# AUX_POWER_-5V.net
KiCad netlist of a schematic drawn in Altium Designer
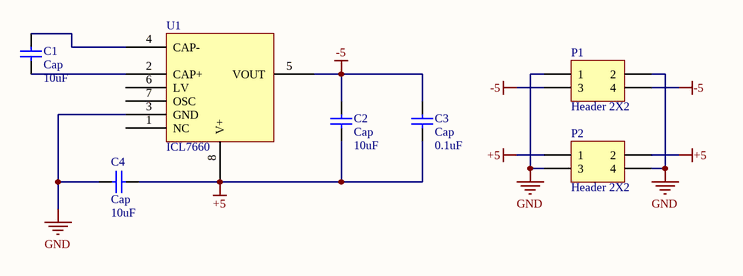
[diagram p0: AUX_POWER_-5V.SchDoc]

(export (version "E")
  (design (tool "Eeschema 10.0.6"))
  (components
    (comp (ref "C1")
      (value "Cap")
      (footprint "C1206")
      (description "Capacitor")
      (fields (field (name "ALTIUM_VALUE") "10uF") (field (name "PUBLISHER") "Altium Limited"))
      (libsource (lib "Miscellaneous Devices") (part "Cap"))
    )
    (comp (ref "C2")
      (value "Cap")
      (footprint "C1206")
      (description "Capacitor")
      (fields (field (name "ALTIUM_VALUE") "10uF") (field (name "PUBLISHER") "Altium Limited"))
      (libsource (lib "Miscellaneous Devices") (part "Cap"))
    )
    (comp (ref "C3")
      (value "Cap")
      (footprint "C1206")
      (description "Capacitor")
      (fields (field (name "ALTIUM_VALUE") "0.1uF") (field (name "PUBLISHER") "Altium Limited"))
      (libsource (lib "Miscellaneous Devices") (part "Cap"))
    )
    (comp (ref "C4")
      (value "Cap")
      (footprint "C1206")
      (description "Capacitor")
      (fields (field (name "ALTIUM_VALUE") "10uF") (field (name "PUBLISHER") "Altium Limited"))
      (libsource (lib "Miscellaneous Devices") (part "Cap"))
    )
    (comp (ref "P1")
      (value "Header 2X2")
      (footprint "HDR2X2")
      (description "Header, 2-Pin, Dual row")
      (fields (field (name "PUBLISHER") "Altium Limited"))
      (libsource (lib "Miscellaneous Connectors") (part "Header 2X2"))
    )
    (comp (ref "P2")
      (value "Header 2X2")
      (footprint "HDR2X2")
      (description "Header, 2-Pin, Dual row")
      (fields (field (name "PUBLISHER") "Altium Limited"))
      (libsource (lib "Miscellaneous Connectors") (part "Header 2X2"))
    )
    (comp (ref "U1") (value "ICL7660") (footprint "DIP-8") (libsource (lib "Library") (part "ICL7660")))
  )
  (nets
    (net (code "1") (name "+5") (class "Default")
      (node (ref "C2") (pin "1") (pinfunction "1_1") (pintype "passive"))
      (node (ref "C3") (pin "1") (pinfunction "1_1") (pintype "passive"))
      (node (ref "C4") (pin "1") (pinfunction "1_1") (pintype "passive"))
      (node (ref "P2") (pin "1") (pinfunction "1_1") (pintype "passive"))
      (node (ref "P2") (pin "2") (pinfunction "2_2") (pintype "passive"))
      (node (ref "U1") (pin "8") (pinfunction "V+_8") (pintype "passive"))
    )
    (net (code "2") (name "-5") (class "Default")
      (node (ref "C2") (pin "2") (pinfunction "2_2") (pintype "passive"))
      (node (ref "C3") (pin "2") (pinfunction "2_2") (pintype "passive"))
      (node (ref "P1") (pin "3") (pinfunction "3_3") (pintype "passive"))
      (node (ref "P1") (pin "4") (pinfunction "4_4") (pintype "passive"))
      (node (ref "U1") (pin "5") (pinfunction "VOUT_5") (pintype "passive"))
    )
    (net (code "3") (name "GND") (class "Default")
      (node (ref "C4") (pin "2") (pinfunction "2_2") (pintype "passive"))
      (node (ref "P1") (pin "1") (pinfunction "1_1") (pintype "passive"))
      (node (ref "P1") (pin "2") (pinfunction "2_2") (pintype "passive"))
      (node (ref "P2") (pin "3") (pinfunction "3_3") (pintype "passive"))
      (node (ref "P2") (pin "4") (pinfunction "4_4") (pintype "passive"))
      (node (ref "U1") (pin "3") (pinfunction "GND_3") (pintype "passive"))
    )
    (net (code "4") (name "Net-(U1-CAP+)") (class "Default")
      (node (ref "C1") (pin "1") (pinfunction "1_1") (pintype "passive"))
      (node (ref "U1") (pin "2") (pinfunction "CAP+_2") (pintype "passive"))
    )
    (net (code "5") (name "Net-(U1-CAP-)") (class "Default")
      (node (ref "C1") (pin "2") (pinfunction "2_2") (pintype "passive"))
      (node (ref "U1") (pin "4") (pinfunction "CAP-_4") (pintype "passive"))
    )
    (net (code "6") (name "unconnected-(U1-LV-Pad6)") (class "Default")
      (node (ref "U1") (pin "6") (pinfunction "LV_6") (pintype "passive"))
    )
    (net (code "7") (name "unconnected-(U1-NC-Pad1)") (class "Default")
      (node (ref "U1") (pin "1") (pinfunction "NC_1") (pintype "passive"))
    )
    (net (code "8") (name "unconnected-(U1-OSC-Pad7)") (class "Default")
      (node (ref "U1") (pin "7") (pinfunction "OSC_7") (pintype "passive"))
    )
  )
)
